# EPS_MPPT_Y_Buck-Boost-Converter.net
KiCad netlist of a schematic drawn in Altium Designer
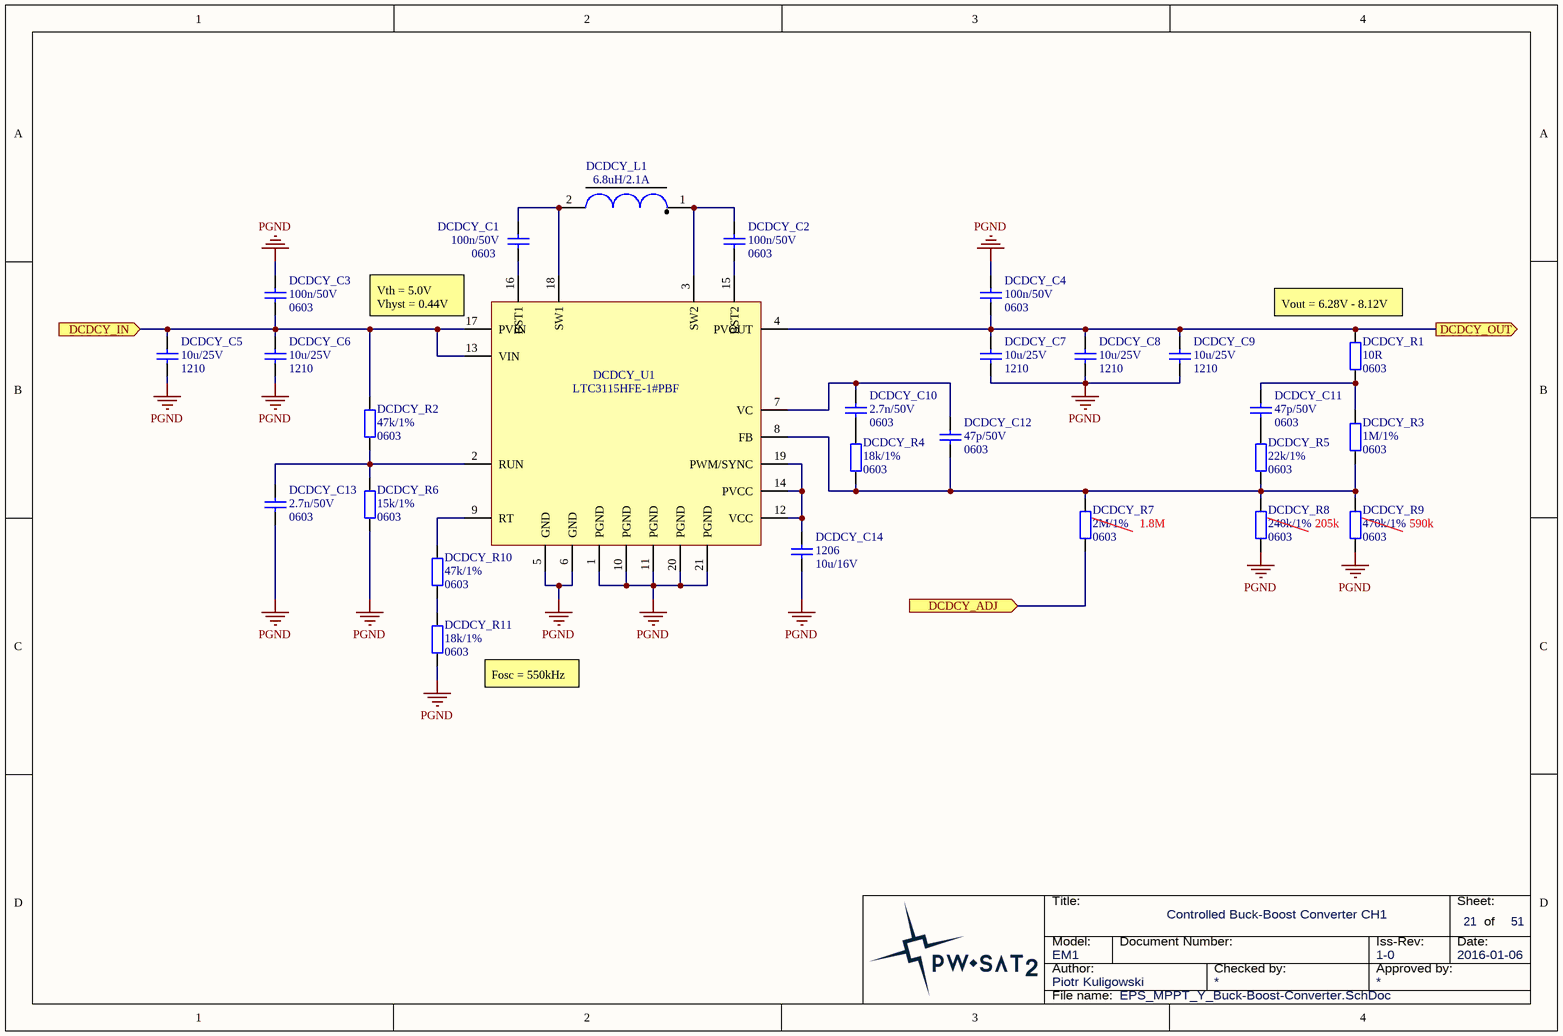
[diagram p0: EPS_MPPT_Y_Buck-Boost-Converter.SchDoc]

(export (version "E")
  (design (tool "Eeschema 10.0.6"))
  (components
    (comp (ref "DCDCY_C1")
      (value "100n/50V")
      (footprint "SMD_Capacitor_0603")
      (description "Ceramic Cap Kemet COTS 100n/50V X7R 0603")
      (fields
        (field (name "MANUFACTURER") "Kemet")
        (field (name "MANUFACTURERPARTNUMBER") "C0603T104K5RALTU")
        (field (name "PACKAGE") "0603")
      )
      (libsource (lib "capacitors") (part "Cer_C0603T104K5RALTU"))
    )
    (comp (ref "DCDCY_C2")
      (value "100n/50V")
      (footprint "SMD_Capacitor_0603")
      (description "Ceramic Cap Kemet COTS 100n/50V X7R 0603")
      (fields
        (field (name "MANUFACTURER") "Kemet")
        (field (name "MANUFACTURERPARTNUMBER") "C0603T104K5RALTU")
        (field (name "PACKAGE") "0603")
      )
      (libsource (lib "capacitors") (part "Cer_C0603T104K5RALTU"))
    )
    (comp (ref "DCDCY_C3")
      (value "100n/50V")
      (footprint "SMD_Capacitor_0603")
      (description "Ceramic Cap Kemet COTS 100n/50V X7R 0603")
      (fields
        (field (name "MANUFACTURER") "Kemet")
        (field (name "MANUFACTURERPARTNUMBER") "C0603T104K5RALTU")
        (field (name "PACKAGE") "0603")
      )
      (libsource (lib "capacitors") (part "Cer_C0603T104K5RALTU"))
    )
    (comp (ref "DCDCY_C4")
      (value "100n/50V")
      (footprint "SMD_Capacitor_0603")
      (description "Ceramic Cap Kemet COTS 100n/50V X7R 0603")
      (fields
        (field (name "MANUFACTURER") "Kemet")
        (field (name "MANUFACTURERPARTNUMBER") "C0603T104K5RALTU")
        (field (name "PACKAGE") "0603")
      )
      (libsource (lib "capacitors") (part "Cer_C0603T104K5RALTU"))
    )
    (comp (ref "DCDCY_C5")
      (value "10u/25V")
      (footprint "SMD_Capacitor_1210")
      (description "Ceramic Cap Murata Automotive 10u/25V X7R 1210")
      (fields
        (field (name "MANUFACTURER") "Murata")
        (field (name "MANUFACTURERPARTNUMBER") "GCJ32ER71E106KA12L")
        (field (name "PACKAGE") "1210")
      )
      (libsource (lib "capacitors") (part "Cer_GCJ32ER71E106KA12L"))
    )
    (comp (ref "DCDCY_C6")
      (value "10u/25V")
      (footprint "SMD_Capacitor_1210")
      (description "Ceramic Cap Murata Automotive 10u/25V X7R 1210")
      (fields
        (field (name "MANUFACTURER") "Murata")
        (field (name "MANUFACTURERPARTNUMBER") "GCJ32ER71E106KA12L")
        (field (name "PACKAGE") "1210")
      )
      (libsource (lib "capacitors") (part "Cer_GCJ32ER71E106KA12L"))
    )
    (comp (ref "DCDCY_C7")
      (value "10u/25V")
      (footprint "SMD_Capacitor_1210")
      (description "Ceramic Cap Murata Automotive 10u/25V X7R 1210")
      (fields
        (field (name "MANUFACTURER") "Murata")
        (field (name "MANUFACTURERPARTNUMBER") "GCJ32ER71E106KA12L")
        (field (name "PACKAGE") "1210")
      )
      (libsource (lib "capacitors") (part "Cer_GCJ32ER71E106KA12L"))
    )
    (comp (ref "DCDCY_C8")
      (value "10u/25V")
      (footprint "SMD_Capacitor_1210")
      (description "Ceramic Cap Murata Automotive 10u/25V X7R 1210")
      (fields
        (field (name "MANUFACTURER") "Murata")
        (field (name "MANUFACTURERPARTNUMBER") "GCJ32ER71E106KA12L")
        (field (name "PACKAGE") "1210")
      )
      (libsource (lib "capacitors") (part "Cer_GCJ32ER71E106KA12L"))
    )
    (comp (ref "DCDCY_C9")
      (value "10u/25V")
      (footprint "SMD_Capacitor_1210")
      (description "Ceramic Cap Murata Automotive 10u/25V X7R 1210")
      (fields
        (field (name "MANUFACTURER") "Murata")
        (field (name "MANUFACTURERPARTNUMBER") "GCJ32ER71E106KA12L")
        (field (name "PACKAGE") "1210")
      )
      (libsource (lib "capacitors") (part "Cer_GCJ32ER71E106KA12L"))
    )
    (comp (ref "DCDCY_C10")
      (value "2.7n/50V")
      (footprint "SMD_Capacitor_0603")
      (description "Cap")
      (fields (field (name "PACKAGE") "0603"))
      (libsource (lib "capacitors") (part "Cap"))
    )
    (comp (ref "DCDCY_C11")
      (value "47p/50V")
      (footprint "SMD_Capacitor_0603")
      (description "Cap")
      (fields (field (name "PACKAGE") "0603"))
      (libsource (lib "capacitors") (part "Cap"))
    )
    (comp (ref "DCDCY_C12")
      (value "47p/50V")
      (footprint "SMD_Capacitor_0603")
      (description "Cap")
      (fields (field (name "PACKAGE") "0603"))
      (libsource (lib "capacitors") (part "Cap"))
    )
    (comp (ref "DCDCY_C13")
      (value "2.7n/50V")
      (footprint "SMD_Capacitor_0603")
      (description "Cap")
      (fields (field (name "PACKAGE") "0603"))
      (libsource (lib "capacitors") (part "Cap"))
    )
    (comp (ref "DCDCY_C14")
      (value "10u/16V")
      (footprint "SMD_Capacitor_1206")
      (description "Ceramic Cap Kemet COTS 10u/16V X7R 1206")
      (fields
        (field (name "MANUFACTURERPARTNUMBER") "C1206T106K4RACTU")
        (field (name "MANUFACTURER") "Kemet")
        (field (name "PACKGE") "1206")
      )
      (libsource (lib "capacitors") (part "Cer_C1206T106K4RACTU"))
    )
    (comp (ref "DCDCY_L1")
      (value "6.8uH/2.1A")
      (footprint "Coilcraft_MSS6132")
      (description "Coilcraft MSS6132 Inductor, L=6.8uH, Irise20deg=2.1A, ESR=52mR, SRF=47MHz.")
      (fields
        (field (name "MANUFACTURER") "Coilcraft")
        (field (name "MANUFACTURERPARTNUMBER") "MSS6132-682MLx")
      )
      (libsource (lib "inductors") (part "MSS6132-682MLx"))
    )
    (comp (ref "DCDCY_R1")
      (value "10R")
      (footprint "SMD_Resistor_0603")
      (fields (field (name "PACKAGE") "0603"))
      (libsource (lib "resistors") (part "Res"))
    )
    (comp (ref "DCDCY_R2")
      (value "47k/1%")
      (footprint "SMD_Resistor_0603")
      (fields (field (name "PACKAGE") "0603"))
      (libsource (lib "resistors") (part "Res"))
    )
    (comp (ref "DCDCY_R3")
      (value "1M/1%")
      (footprint "SMD_Resistor_0603")
      (fields (field (name "PACKAGE") "0603"))
      (libsource (lib "resistors") (part "Res"))
    )
    (comp (ref "DCDCY_R4")
      (value "18k/1%")
      (footprint "SMD_Resistor_0603")
      (fields (field (name "PACKAGE") "0603"))
      (libsource (lib "resistors") (part "Res"))
    )
    (comp (ref "DCDCY_R5")
      (value "22k/1%")
      (footprint "SMD_Resistor_0603")
      (fields (field (name "PACKAGE") "0603"))
      (libsource (lib "resistors") (part "Res"))
    )
    (comp (ref "DCDCY_R6")
      (value "15k/1%")
      (footprint "SMD_Resistor_0603")
      (fields (field (name "PACKAGE") "0603"))
      (libsource (lib "resistors") (part "Res"))
    )
    (comp (ref "DCDCY_R7")
      (value "2M/1%")
      (footprint "SMD_Resistor_0603")
      (description "2M/1% Vishay CRCW 0603 Resistor. 100mW, 200ppm, 75V.")
      (fields
        (field (name "MANUFACTURERPARTNUMBER") "CRCW06032M00FKxxxx")
        (field (name "MANUFACTURER") "Vishay")
        (field (name "PACKAGE") "0603")
      )
      (libsource (lib "resistors") (part "CRCW06032M00FKxxxx"))
    )
    (comp (ref "DCDCY_R8")
      (value "240k/1%")
      (footprint "SMD_Resistor_0603")
      (fields (field (name "PACKAGE") "0603"))
      (libsource (lib "resistors") (part "Res"))
    )
    (comp (ref "DCDCY_R9")
      (value "470k/1%")
      (footprint "SMD_Resistor_0603")
      (fields (field (name "PACKAGE") "0603"))
      (libsource (lib "resistors") (part "Res"))
    )
    (comp (ref "DCDCY_R10")
      (value "47k/1%")
      (footprint "SMD_Resistor_0603")
      (fields (field (name "PACKAGE") "0603"))
      (libsource (lib "resistors") (part "Res"))
    )
    (comp (ref "DCDCY_R11")
      (value "18k/1%")
      (footprint "SMD_Resistor_0603")
      (fields (field (name "PACKAGE") "0603"))
      (libsource (lib "resistors") (part "Res"))
    )
    (comp (ref "DCDCY_U1")
      (value "LTC3115HFE-1#PBF")
      (footprint "LT-FE-20-EPV-CA_N")
      (fields (field (name "MANUFACTURER") "Linear Technology"))
      (libsource (lib "microcircuits") (part "LTC3115HFE-1#PBF"))
    )
  )
  (nets
    (net (code "1") (name "/DCDCY_ADJ") (class "Default")
      (node (ref "DCDCY_R7") (pin "1") (pinfunction "1_1") (pintype "passive"))
    )
    (net (code "2") (name "/DCDCY_IN") (class "Default")
      (node (ref "DCDCY_C3") (pin "2") (pinfunction "2_2") (pintype "passive"))
      (node (ref "DCDCY_C5") (pin "1") (pinfunction "1_1") (pintype "passive"))
      (node (ref "DCDCY_C6") (pin "1") (pinfunction "1_1") (pintype "passive"))
      (node (ref "DCDCY_R2") (pin "1") (pinfunction "1_1") (pintype "passive"))
      (node (ref "DCDCY_U1") (pin "13") (pinfunction "VIN_13") (pintype "passive"))
      (node (ref "DCDCY_U1") (pin "17") (pinfunction "PVIN_17") (pintype "passive"))
    )
    (net (code "3") (name "/DCDCY_OUT") (class "Default")
      (node (ref "DCDCY_C4") (pin "2") (pinfunction "2_2") (pintype "passive"))
      (node (ref "DCDCY_C7") (pin "1") (pinfunction "1_1") (pintype "passive"))
      (node (ref "DCDCY_C8") (pin "1") (pinfunction "1_1") (pintype "passive"))
      (node (ref "DCDCY_C9") (pin "1") (pinfunction "1_1") (pintype "passive"))
      (node (ref "DCDCY_R1") (pin "1") (pinfunction "1_1") (pintype "passive"))
      (node (ref "DCDCY_U1") (pin "4") (pinfunction "PVOUT_4") (pintype "passive"))
    )
    (net (code "4") (name "Net-(DCDCY_C10-Pad2)") (class "Default")
      (node (ref "DCDCY_C10") (pin "2") (pinfunction "2_2") (pintype "passive"))
      (node (ref "DCDCY_R4") (pin "1") (pinfunction "1_1") (pintype "passive"))
    )
    (net (code "5") (name "Net-(DCDCY_C11-Pad1)") (class "Default")
      (node (ref "DCDCY_C11") (pin "1") (pinfunction "1_1") (pintype "passive"))
      (node (ref "DCDCY_R1") (pin "2") (pinfunction "2_2") (pintype "passive"))
      (node (ref "DCDCY_R3") (pin "1") (pinfunction "1_1") (pintype "passive"))
    )
    (net (code "6") (name "Net-(DCDCY_C11-Pad2)") (class "Default")
      (node (ref "DCDCY_C11") (pin "2") (pinfunction "2_2") (pintype "passive"))
      (node (ref "DCDCY_R5") (pin "1") (pinfunction "1_1") (pintype "passive"))
    )
    (net (code "7") (name "Net-(DCDCY_R10-Pad2)") (class "Default")
      (node (ref "DCDCY_R10") (pin "2") (pinfunction "2_2") (pintype "passive"))
      (node (ref "DCDCY_R11") (pin "1") (pinfunction "1_1") (pintype "passive"))
    )
    (net (code "8") (name "Net-(DCDCY_U1-BST1)") (class "Default")
      (node (ref "DCDCY_C1") (pin "2") (pinfunction "2_2") (pintype "passive"))
      (node (ref "DCDCY_U1") (pin "16") (pinfunction "BST1_16") (pintype "passive"))
    )
    (net (code "9") (name "Net-(DCDCY_U1-BST2)") (class "Default")
      (node (ref "DCDCY_C2") (pin "2") (pinfunction "2_2") (pintype "passive"))
      (node (ref "DCDCY_U1") (pin "15") (pinfunction "BST2_15") (pintype "passive"))
    )
    (net (code "10") (name "Net-(DCDCY_U1-FB)") (class "Default")
      (node (ref "DCDCY_C12") (pin "2") (pinfunction "2_2") (pintype "passive"))
      (node (ref "DCDCY_R3") (pin "2") (pinfunction "2_2") (pintype "passive"))
      (node (ref "DCDCY_R4") (pin "2") (pinfunction "2_2") (pintype "passive"))
      (node (ref "DCDCY_R5") (pin "2") (pinfunction "2_2") (pintype "passive"))
      (node (ref "DCDCY_R7") (pin "2") (pinfunction "2_2") (pintype "passive"))
      (node (ref "DCDCY_R8") (pin "1") (pinfunction "1_1") (pintype "passive"))
      (node (ref "DCDCY_R9") (pin "1") (pinfunction "1_1") (pintype "passive"))
      (node (ref "DCDCY_U1") (pin "8") (pinfunction "FB_8") (pintype "passive"))
    )
    (net (code "11") (name "Net-(DCDCY_U1-PVCC)") (class "Default")
      (node (ref "DCDCY_C14") (pin "1") (pinfunction "1_1") (pintype "passive"))
      (node (ref "DCDCY_U1") (pin "12") (pinfunction "VCC_12") (pintype "passive"))
      (node (ref "DCDCY_U1") (pin "14") (pinfunction "PVCC_14") (pintype "passive"))
      (node (ref "DCDCY_U1") (pin "19") (pinfunction "PWM/SYNC_19") (pintype "passive"))
    )
    (net (code "12") (name "Net-(DCDCY_U1-RT)") (class "Default")
      (node (ref "DCDCY_R10") (pin "1") (pinfunction "1_1") (pintype "passive"))
      (node (ref "DCDCY_U1") (pin "9") (pinfunction "RT_9") (pintype "passive"))
    )
    (net (code "13") (name "Net-(DCDCY_U1-RUN)") (class "Default")
      (node (ref "DCDCY_C13") (pin "1") (pinfunction "1_1") (pintype "passive"))
      (node (ref "DCDCY_R2") (pin "2") (pinfunction "2_2") (pintype "passive"))
      (node (ref "DCDCY_R6") (pin "1") (pinfunction "1_1") (pintype "passive"))
      (node (ref "DCDCY_U1") (pin "2") (pinfunction "RUN_2") (pintype "passive"))
    )
    (net (code "14") (name "Net-(DCDCY_U1-SW1)") (class "Default")
      (node (ref "DCDCY_C1") (pin "1") (pinfunction "1_1") (pintype "passive"))
      (node (ref "DCDCY_L1") (pin "2") (pinfunction "2_2") (pintype "passive"))
      (node (ref "DCDCY_U1") (pin "18") (pinfunction "SW1_18") (pintype "passive"))
    )
    (net (code "15") (name "Net-(DCDCY_U1-SW2)") (class "Default")
      (node (ref "DCDCY_C2") (pin "1") (pinfunction "1_1") (pintype "passive"))
      (node (ref "DCDCY_L1") (pin "1") (pinfunction "1_1") (pintype "passive"))
      (node (ref "DCDCY_U1") (pin "3") (pinfunction "SW2_3") (pintype "passive"))
    )
    (net (code "16") (name "Net-(DCDCY_U1-VC)") (class "Default")
      (node (ref "DCDCY_C10") (pin "1") (pinfunction "1_1") (pintype "passive"))
      (node (ref "DCDCY_C12") (pin "1") (pinfunction "1_1") (pintype "passive"))
      (node (ref "DCDCY_U1") (pin "7") (pinfunction "VC_7") (pintype "passive"))
    )
    (net (code "17") (name "PGND") (class "Default")
      (node (ref "DCDCY_C13") (pin "2") (pinfunction "2_2") (pintype "passive"))
      (node (ref "DCDCY_C14") (pin "2") (pinfunction "2_2") (pintype "passive"))
      (node (ref "DCDCY_C3") (pin "1") (pinfunction "1_1") (pintype "passive"))
      (node (ref "DCDCY_C4") (pin "1") (pinfunction "1_1") (pintype "passive"))
      (node (ref "DCDCY_C5") (pin "2") (pinfunction "2_2") (pintype "passive"))
      (node (ref "DCDCY_C6") (pin "2") (pinfunction "2_2") (pintype "passive"))
      (node (ref "DCDCY_C7") (pin "2") (pinfunction "2_2") (pintype "passive"))
      (node (ref "DCDCY_C8") (pin "2") (pinfunction "2_2") (pintype "passive"))
      (node (ref "DCDCY_C9") (pin "2") (pinfunction "2_2") (pintype "passive"))
      (node (ref "DCDCY_R11") (pin "2") (pinfunction "2_2") (pintype "passive"))
      (node (ref "DCDCY_R6") (pin "2") (pinfunction "2_2") (pintype "passive"))
      (node (ref "DCDCY_R8") (pin "2") (pinfunction "2_2") (pintype "passive"))
      (node (ref "DCDCY_R9") (pin "2") (pinfunction "2_2") (pintype "passive"))
      (node (ref "DCDCY_U1") (pin "1") (pinfunction "PGND_1") (pintype "passive"))
      (node (ref "DCDCY_U1") (pin "10") (pinfunction "PGND_10") (pintype "passive"))
      (node (ref "DCDCY_U1") (pin "11") (pinfunction "PGND_11") (pintype "passive"))
      (node (ref "DCDCY_U1") (pin "20") (pinfunction "PGND_20") (pintype "passive"))
      (node (ref "DCDCY_U1") (pin "21") (pinfunction "PGND_21") (pintype "passive"))
      (node (ref "DCDCY_U1") (pin "5") (pinfunction "GND_5") (pintype "passive"))
      (node (ref "DCDCY_U1") (pin "6") (pinfunction "GND_6") (pintype "passive"))
    )
  )
)
